# greenhousectrl-latest-expanded.net
KiCad netlist of a schematic drawn in EAGLE
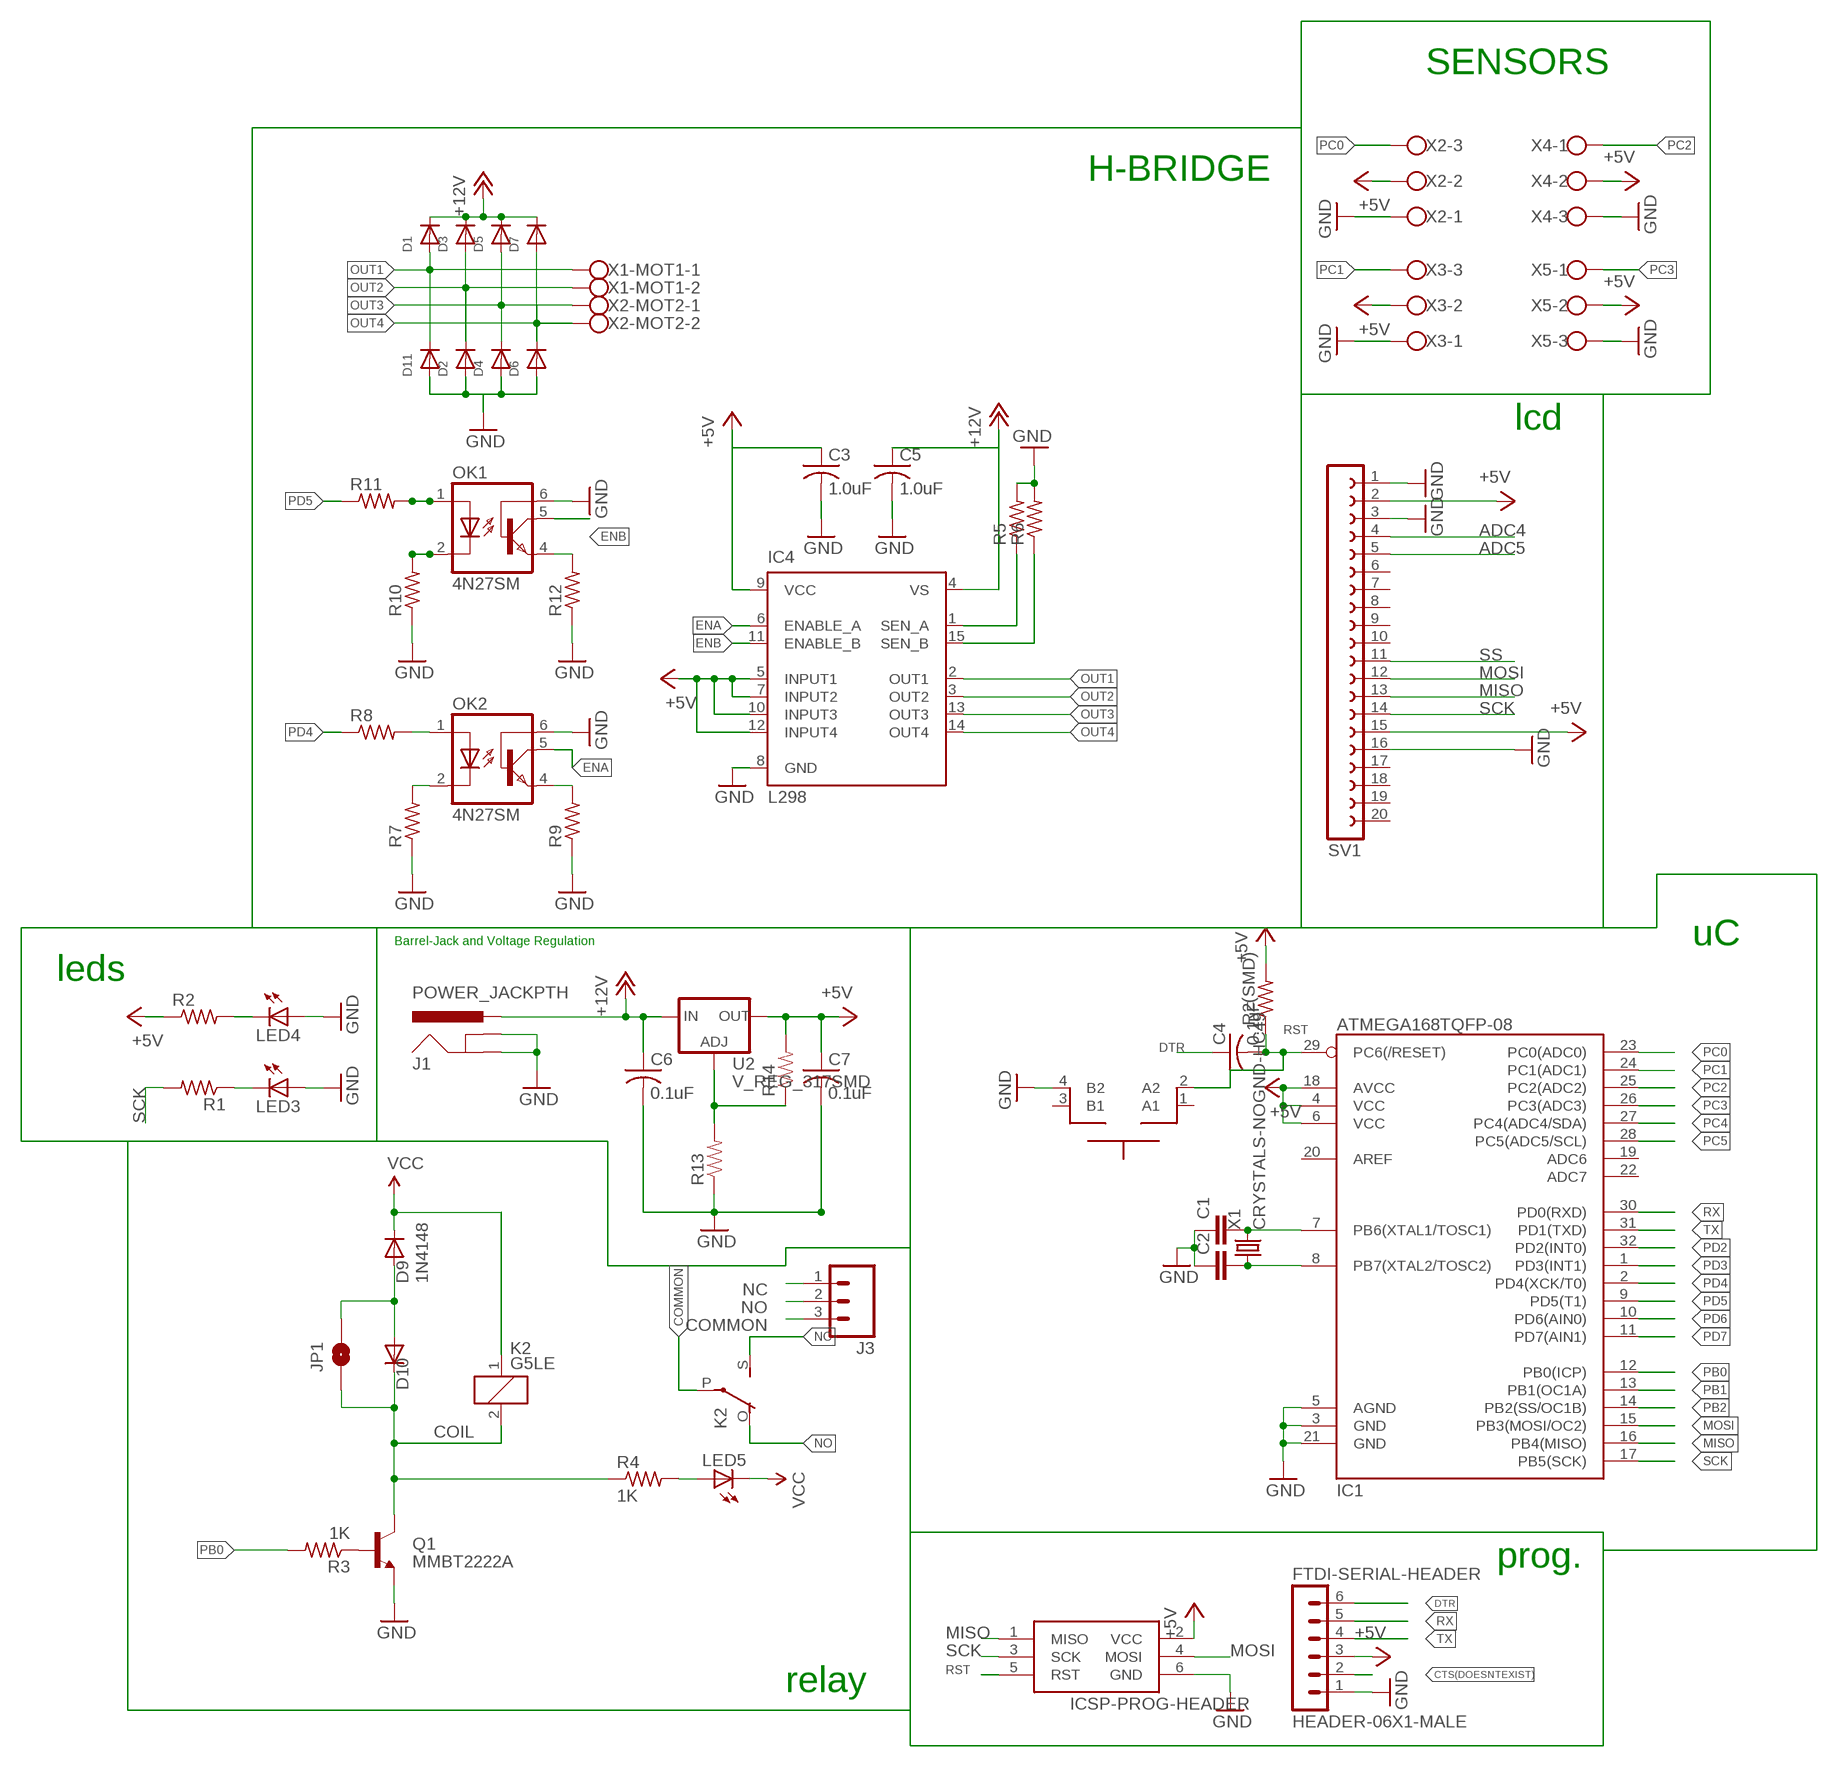
[diagram p0: schematic, sheet 1]

(export (version "E")
  (design (tool "Eeschema 10.0.6"))
  (components
    (comp (ref "C1")
      (value "C-EUC0805")
      (footprint "eagle-import:C0805")
      (libsource (lib "eagle-import") (part "C-EUC0805"))
    )
    (comp (ref "C2")
      (value "C-EUC0805")
      (footprint "eagle-import:C0805")
      (libsource (lib "eagle-import") (part "C-EUC0805"))
    )
    (comp (ref "C3")
      (value "1.0uF")
      (footprint "eagle-import:C0805")
      (libsource (lib "eagle-import") (part "C-USC0805"))
    )
    (comp (ref "C4")
      (value "0.1uF")
      (footprint "eagle-import:C0805")
      (libsource (lib "eagle-import") (part "C-USC0805"))
    )
    (comp (ref "C5")
      (value "1.0uF")
      (footprint "eagle-import:C0805")
      (libsource (lib "eagle-import") (part "C-USC0805"))
    )
    (comp (ref "C6")
      (value "0.1uF")
      (footprint "eagle-import:C0805")
      (libsource (lib "eagle-import") (part "C-USC0805"))
    )
    (comp (ref "C7")
      (value "0.1uF")
      (footprint "eagle-import:C0805")
      (libsource (lib "eagle-import") (part "C-USC0805"))
    )
    (comp (ref "D1")
      (value "DIODESOD-523")
      (footprint "eagle-import:SOD-523")
      (libsource (lib "eagle-import") (part "DIODESOD-523"))
    )
    (comp (ref "D2")
      (value "DIODESOD-523")
      (footprint "eagle-import:SOD-523")
      (libsource (lib "eagle-import") (part "DIODESOD-523"))
    )
    (comp (ref "D3")
      (value "DIODESOD-523")
      (footprint "eagle-import:SOD-523")
      (libsource (lib "eagle-import") (part "DIODESOD-523"))
    )
    (comp (ref "D4")
      (value "DIODESOD-523")
      (footprint "eagle-import:SOD-523")
      (libsource (lib "eagle-import") (part "DIODESOD-523"))
    )
    (comp (ref "D5")
      (value "DIODESOD-523")
      (footprint "eagle-import:SOD-523")
      (libsource (lib "eagle-import") (part "DIODESOD-523"))
    )
    (comp (ref "D6")
      (value "DIODESOD-523")
      (footprint "eagle-import:SOD-523")
      (libsource (lib "eagle-import") (part "DIODESOD-523"))
    )
    (comp (ref "D7")
      (value "DIODESOD-523")
      (footprint "eagle-import:SOD-523")
      (libsource (lib "eagle-import") (part "DIODESOD-523"))
    )
    (comp (ref "D9")
      (value "1N4148")
      (footprint "eagle-import:SOD-323F")
      (libsource (lib "eagle-import") (part "DIODESOD-323F"))
    )
    (comp (ref "D10")
      (value "Zener")
      (footprint "eagle-import:SOD-323F")
      (libsource (lib "eagle-import") (part "DIODESOD-323F"))
    )
    (comp (ref "D11")
      (value "DIODESOD-523")
      (footprint "eagle-import:SOD-523")
      (libsource (lib "eagle-import") (part "DIODESOD-523"))
    )
    (comp (ref "FTDI-SERIAL-HEADER")
      (value "HEADER-06X1-MALE")
      (footprint "eagle-import:06X1-PTH")
      (libsource (lib "eagle-import") (part "HEADER-06X1?-MALE"))
    )
    (comp (ref "IC1")
      (value "ATMEGA168TQFP-08")
      (footprint "eagle-import:TQFP32-08")
      (libsource (lib "eagle-import") (part "ATMEGA168TQFP-08"))
    )
    (comp (ref "IC4")
      (value "L298")
      (footprint "eagle-import:MULTIWATT-15")
      (fields (field (name "MPN") "L298N"))
      (libsource (lib "eagle-import") (part "L298"))
    )
    (comp (ref "ICSP-PROG-HEADER")
      (value "AVRISP-6")
      (footprint "eagle-import:AVRISP")
      (libsource (lib "eagle-import") (part "AVRISP-6"))
    )
    (comp (ref "J1")
      (value "POWER_JACKPTH")
      (footprint "eagle-import:POWER_JACK_PTH")
      (libsource (lib "eagle-import") (part "POWER_JACKPTH"))
    )
    (comp (ref "J3")
      (value "M03-SCREW-5MM")
      (footprint "eagle-import:SCREWTERMINAL-5MM-3")
      (libsource (lib "eagle-import") (part "M03-SCREW-5MM"))
    )
    (comp (ref "JP1")
      (value "JUMPER-PAD-2-NOYES_SILK")
      (footprint "eagle-import:PAD-JUMPER-2-NO_YES_SILK")
      (libsource (lib "eagle-import") (part "JUMPER-PAD-2-NOYES_SILK"))
    )
    (comp (ref "K2")
      (value "G5LE")
      (footprint "eagle-import:G5LE")
      (libsource (lib "eagle-import") (part "G5LE"))
    )
    (comp (ref "LED3")
      (value "LEDCHIP-LED0805")
      (footprint "eagle-import:CHIP-LED0805")
      (libsource (lib "eagle-import") (part "LEDCHIP-LED0805"))
    )
    (comp (ref "LED4")
      (value "LEDCHIP-LED0805")
      (footprint "eagle-import:CHIP-LED0805")
      (libsource (lib "eagle-import") (part "LEDCHIP-LED0805"))
    )
    (comp (ref "LED5")
      (value "LEDCHIP-LED0805")
      (footprint "eagle-import:CHIP-LED0805")
      (libsource (lib "eagle-import") (part "LEDCHIP-LED0805"))
    )
    (comp (ref "OK1")
      (value "4N27SM")
      (footprint "eagle-import:DIL6-SMD")
      (fields (field (name "MF") "FAIRCHILD SEMICONDUCTOR") (field (name "MPN") "4N27S-M"))
      (libsource (lib "eagle-import") (part "4N?MS27"))
    )
    (comp (ref "OK2")
      (value "4N27SM")
      (footprint "eagle-import:DIL6-SMD")
      (fields (field (name "MF") "FAIRCHILD SEMICONDUCTOR") (field (name "MPN") "4N27S-M"))
      (libsource (lib "eagle-import") (part "4N?MS27"))
    )
    (comp (ref "Q1")
      (value "MMBT2222A")
      (footprint "eagle-import:SOT23-3")
      (libsource (lib "eagle-import") (part "TRANSISTOR_NPNMMBT2222A"))
    )
    (comp (ref "R1")
      (value "R-US_M0805")
      (footprint "eagle-import:M0805")
      (libsource (lib "eagle-import") (part "R-US_M0805"))
    )
    (comp (ref "R2")
      (value "R-US_M0805")
      (footprint "eagle-import:M0805")
      (libsource (lib "eagle-import") (part "R-US_M0805"))
    )
    (comp (ref "R2(SMD)")
      (value "R-US_M0805")
      (footprint "eagle-import:M0805")
      (libsource (lib "eagle-import") (part "R-US_M0805"))
    )
    (comp (ref "R3")
      (value "1K")
      (footprint "eagle-import:M0805")
      (libsource (lib "eagle-import") (part "R-US_M0805"))
    )
    (comp (ref "R4")
      (value "1K")
      (footprint "eagle-import:M0805")
      (libsource (lib "eagle-import") (part "R-US_M0805"))
    )
    (comp (ref "R5")
      (value "R-US_M0805")
      (footprint "eagle-import:M0805")
      (libsource (lib "eagle-import") (part "R-US_M0805"))
    )
    (comp (ref "R6")
      (value "R-US_M0805")
      (footprint "eagle-import:M0805")
      (libsource (lib "eagle-import") (part "R-US_M0805"))
    )
    (comp (ref "R7")
      (value "R-US_M0805")
      (footprint "eagle-import:M0805")
      (libsource (lib "eagle-import") (part "R-US_M0805"))
    )
    (comp (ref "R8")
      (value "R-US_M0805")
      (footprint "eagle-import:M0805")
      (libsource (lib "eagle-import") (part "R-US_M0805"))
    )
    (comp (ref "R9")
      (value "R-US_M0805")
      (footprint "eagle-import:M0805")
      (libsource (lib "eagle-import") (part "R-US_M0805"))
    )
    (comp (ref "R10")
      (value "R-US_M0805")
      (footprint "eagle-import:M0805")
      (libsource (lib "eagle-import") (part "R-US_M0805"))
    )
    (comp (ref "R11")
      (value "R-US_M0805")
      (footprint "eagle-import:M0805")
      (libsource (lib "eagle-import") (part "R-US_M0805"))
    )
    (comp (ref "R12")
      (value "R-US_M0805")
      (footprint "eagle-import:M0805")
      (libsource (lib "eagle-import") (part "R-US_M0805"))
    )
    (comp (ref "R13")
      (value "RESISTOR0402")
      (footprint "eagle-import:0402-RES")
      (libsource (lib "eagle-import") (part "RESISTOR0402"))
    )
    (comp (ref "R14")
      (value "RESISTOR0402")
      (footprint "eagle-import:0402-RES")
      (libsource (lib "eagle-import") (part "RESISTOR0402"))
    )
    (comp (ref "SV1")
      (value "FE20-1")
      (footprint "eagle-import:FE20")
      (libsource (lib "eagle-import") (part "FE20-1"))
    )
    (comp (ref "SW2")
      (value "MOMENTARYBUTTON")
      (footprint "eagle-import:SPST_NO_SMD")
      (libsource (lib "eagle-import") (part "MOMENTARYBUTTON"))
    )
    (comp (ref "U2")
      (value "V_REG_317SMD")
      (footprint "eagle-import:SOT223")
      (libsource (lib "eagle-import") (part "V_REG_317SMD"))
    )
    (comp (ref "X1")
      (value "CRYSTALS-NOGND-HC49")
      (footprint "eagle-import:HC49")
      (libsource (lib "eagle-import") (part "CRYSTALS-NOGND-HC49"))
    )
    (comp (ref "X1-MOT1")
      (value "W237-102")
      (footprint "eagle-import:W237-102")
      (fields (field (name "MPN") "237-102"))
      (libsource (lib "eagle-import") (part "W237-102"))
    )
    (comp (ref "X2")
      (value "1X03_5MM_SCREW")
      (footprint "eagle-import:W237-103")
      (fields (field (name "MPN") "237-103"))
      (libsource (lib "eagle-import") (part "1X03_5MM_SCREW"))
    )
    (comp (ref "X2-MOT2")
      (value "W237-102")
      (footprint "eagle-import:W237-102")
      (fields (field (name "MPN") "237-102"))
      (libsource (lib "eagle-import") (part "W237-102"))
    )
    (comp (ref "X3")
      (value "1X03_5MM_SCREW")
      (footprint "eagle-import:W237-103")
      (fields (field (name "MPN") "237-103"))
      (libsource (lib "eagle-import") (part "1X03_5MM_SCREW"))
    )
    (comp (ref "X4")
      (value "1X03_5MM_SCREW")
      (footprint "eagle-import:W237-103")
      (fields (field (name "MPN") "237-103"))
      (libsource (lib "eagle-import") (part "1X03_5MM_SCREW"))
    )
    (comp (ref "X5")
      (value "1X03_5MM_SCREW")
      (footprint "eagle-import:W237-103")
      (fields (field (name "MPN") "237-103"))
      (libsource (lib "eagle-import") (part "1X03_5MM_SCREW"))
    )
  )
  (nets
    (net (code "1") (name "+5V") (class "Default")
      (node (ref "C3") (pin "1") (pinfunction "1_1") (pintype "passive"))
      (node (ref "C7") (pin "1") (pinfunction "1_1") (pintype "passive"))
      (node (ref "FTDI-SERIAL-HEADER") (pin "3") (pinfunction "3_3") (pintype "passive"))
      (node (ref "IC1") (pin "18") (pinfunction "AVCC_18") (pintype "bidirectional"))
      (node (ref "IC1") (pin "4") (pinfunction "VCC_4") (pintype "bidirectional"))
      (node (ref "IC1") (pin "6") (pinfunction "VCC_6") (pintype "bidirectional"))
      (node (ref "IC4") (pin "10") (pinfunction "INPUT3_10") (pintype "input"))
      (node (ref "IC4") (pin "12") (pinfunction "INPUT4_12") (pintype "input"))
      (node (ref "IC4") (pin "5") (pinfunction "INPUT1_5") (pintype "input"))
      (node (ref "IC4") (pin "7") (pinfunction "INPUT2_7") (pintype "input"))
      (node (ref "IC4") (pin "9") (pinfunction "VCC_9") (pintype "power_in"))
      (node (ref "ICSP-PROG-HEADER") (pin "2") (pinfunction "VCC_2") (pintype "power_in"))
      (node (ref "R14") (pin "2") (pinfunction "2_2") (pintype "passive"))
      (node (ref "R2") (pin "1") (pinfunction "1_1") (pintype "passive"))
      (node (ref "R2(SMD)") (pin "2") (pinfunction "2_2") (pintype "passive"))
      (node (ref "SV1") (pin "15") (pinfunction "15_15") (pintype "passive"))
      (node (ref "SV1") (pin "2") (pinfunction "2_2") (pintype "passive"))
      (node (ref "U2") (pin "2") (pinfunction "OUT_2") (pintype "output"))
      (node (ref "X2") (pin "2") (pinfunction "KL_2") (pintype "passive"))
      (node (ref "X3") (pin "2") (pinfunction "KL_2") (pintype "passive"))
      (node (ref "X4") (pin "2") (pinfunction "KL_2") (pintype "passive"))
      (node (ref "X5") (pin "2") (pinfunction "KL_2") (pintype "passive"))
    )
    (net (code "2") (name "+12V") (class "Default")
      (node (ref "C5") (pin "1") (pinfunction "1_1") (pintype "passive"))
      (node (ref "C6") (pin "1") (pinfunction "1_1") (pintype "passive"))
      (node (ref "D1") (pin "K") (pinfunction "C_K") (pintype "passive"))
      (node (ref "D3") (pin "K") (pinfunction "C_K") (pintype "passive"))
      (node (ref "D5") (pin "K") (pinfunction "C_K") (pintype "passive"))
      (node (ref "D7") (pin "K") (pinfunction "C_K") (pintype "passive"))
      (node (ref "IC4") (pin "4") (pinfunction "VS_4") (pintype "power_in"))
      (node (ref "J1") (pin "PWR") (pinfunction "PWR_PWR") (pintype "bidirectional"))
      (node (ref "U2") (pin "3") (pinfunction "IN_3") (pintype "input"))
    )
    (net (code "3") (name "/ADC4") (class "Default")
      (node (ref "SV1") (pin "4") (pinfunction "4_4") (pintype "passive"))
    )
    (net (code "4") (name "/ADC5") (class "Default")
      (node (ref "SV1") (pin "5") (pinfunction "5_5") (pintype "passive"))
    )
    (net (code "5") (name "/COIL") (class "Default")
      (node (ref "D10") (pin "C") (pinfunction "C_C") (pintype "passive"))
      (node (ref "JP1") (pin "1") (pinfunction "1_1") (pintype "passive"))
      (node (ref "K2") (pin "2") (pinfunction "2_2") (pintype "passive"))
      (node (ref "Q1") (pin "3") (pinfunction "C_3") (pintype "passive"))
      (node (ref "R4") (pin "1") (pinfunction "1_1") (pintype "passive"))
    )
    (net (code "6") (name "/RST") (class "Default")
      (node (ref "C4") (pin "2") (pinfunction "2_2") (pintype "passive"))
      (node (ref "IC1") (pin "29") (pinfunction "PC6(/RESET)_29") (pintype "bidirectional"))
      (node (ref "ICSP-PROG-HEADER") (pin "5") (pinfunction "RST_5") (pintype "output"))
      (node (ref "R2(SMD)") (pin "1") (pinfunction "1_1") (pintype "passive"))
      (node (ref "SW2") (pin "2") (pinfunction "A2_2") (pintype "bidirectional"))
    )
    (net (code "7") (name "/SS") (class "Default")
      (node (ref "SV1") (pin "11") (pinfunction "11_11") (pintype "passive"))
    )
    (net (code "8") (name "COMMON") (class "Default")
      (node (ref "J3") (pin "3") (pinfunction "3_3") (pintype "passive"))
      (node (ref "K2") (pin "P") (pinfunction "P_P") (pintype "passive"))
    )
    (net (code "9") (name "CTS(DOESNTEXIST)") (class "Default")
      (node (ref "FTDI-SERIAL-HEADER") (pin "2") (pinfunction "2_2") (pintype "passive"))
    )
    (net (code "10") (name "DTR") (class "Default")
      (node (ref "C4") (pin "1") (pinfunction "1_1") (pintype "passive"))
      (node (ref "FTDI-SERIAL-HEADER") (pin "6") (pinfunction "6_6") (pintype "passive"))
    )
    (net (code "11") (name "ENA") (class "Default")
      (node (ref "IC4") (pin "6") (pinfunction "ENABLE_A_6") (pintype "input"))
      (node (ref "OK2") (pin "5") (pinfunction "COL_5") (pintype "passive"))
    )
    (net (code "12") (name "ENB") (class "Default")
      (node (ref "IC4") (pin "11") (pinfunction "ENABLE_B_11") (pintype "input"))
      (node (ref "OK1") (pin "5") (pinfunction "COL_5") (pintype "passive"))
    )
    (net (code "13") (name "GND") (class "Default")
      (node (ref "C1") (pin "1") (pinfunction "1_1") (pintype "passive"))
      (node (ref "C2") (pin "1") (pinfunction "1_1") (pintype "passive"))
      (node (ref "C3") (pin "2") (pinfunction "2_2") (pintype "passive"))
      (node (ref "C5") (pin "2") (pinfunction "2_2") (pintype "passive"))
      (node (ref "C6") (pin "2") (pinfunction "2_2") (pintype "passive"))
      (node (ref "C7") (pin "2") (pinfunction "2_2") (pintype "passive"))
      (node (ref "D11") (pin "A") (pinfunction "A_A") (pintype "passive"))
      (node (ref "D2") (pin "A") (pinfunction "A_A") (pintype "passive"))
      (node (ref "D4") (pin "A") (pinfunction "A_A") (pintype "passive"))
      (node (ref "D6") (pin "A") (pinfunction "A_A") (pintype "passive"))
      (node (ref "FTDI-SERIAL-HEADER") (pin "1") (pinfunction "1_1") (pintype "passive"))
      (node (ref "IC1") (pin "21") (pinfunction "GND_21") (pintype "bidirectional"))
      (node (ref "IC1") (pin "3") (pinfunction "GND_3") (pintype "bidirectional"))
      (node (ref "IC1") (pin "5") (pinfunction "AGND_5") (pintype "bidirectional"))
      (node (ref "IC4") (pin "8") (pinfunction "GND_8") (pintype "power_in"))
      (node (ref "ICSP-PROG-HEADER") (pin "6") (pinfunction "GND_6") (pintype "power_in"))
      (node (ref "J1") (pin "GND") (pinfunction "GND_GND") (pintype "bidirectional"))
      (node (ref "J1") (pin "GNDBREAK") (pinfunction "GNDBREAK_GNDBREAK") (pintype "bidirectional"))
      (node (ref "LED3") (pin "A") (pinfunction "A_A") (pintype "passive"))
      (node (ref "LED4") (pin "A") (pinfunction "A_A") (pintype "passive"))
      (node (ref "OK1") (pin "6") (pinfunction "BAS_6") (pintype "passive"))
      (node (ref "OK2") (pin "6") (pinfunction "BAS_6") (pintype "passive"))
      (node (ref "Q1") (pin "2") (pinfunction "E_2") (pintype "passive"))
      (node (ref "R10") (pin "1") (pinfunction "1_1") (pintype "passive"))
      (node (ref "R12") (pin "1") (pinfunction "1_1") (pintype "passive"))
      (node (ref "R13") (pin "1") (pinfunction "1_1") (pintype "passive"))
      (node (ref "R5") (pin "2") (pinfunction "2_2") (pintype "passive"))
      (node (ref "R6") (pin "2") (pinfunction "2_2") (pintype "passive"))
      (node (ref "R7") (pin "1") (pinfunction "1_1") (pintype "passive"))
      (node (ref "R9") (pin "1") (pinfunction "1_1") (pintype "passive"))
      (node (ref "SV1") (pin "1") (pinfunction "1_1") (pintype "passive"))
      (node (ref "SV1") (pin "16") (pinfunction "16_16") (pintype "passive"))
      (node (ref "SV1") (pin "3") (pinfunction "3_3") (pintype "passive"))
      (node (ref "SW2") (pin "4") (pinfunction "B2_4") (pintype "bidirectional"))
      (node (ref "X2") (pin "1") (pinfunction "KL_1") (pintype "passive"))
      (node (ref "X3") (pin "1") (pinfunction "KL_1") (pintype "passive"))
      (node (ref "X4") (pin "3") (pinfunction "KL_3") (pintype "passive"))
      (node (ref "X5") (pin "3") (pinfunction "KL_3") (pintype "passive"))
    )
    (net (code "14") (name "MISO") (class "Default")
      (node (ref "IC1") (pin "16") (pinfunction "PB4(MISO)_16") (pintype "bidirectional"))
      (node (ref "ICSP-PROG-HEADER") (pin "1") (pinfunction "MISO_1") (pintype "input"))
      (node (ref "SV1") (pin "13") (pinfunction "13_13") (pintype "passive"))
    )
    (net (code "15") (name "MOSI") (class "Default")
      (node (ref "IC1") (pin "15") (pinfunction "PB3(MOSI/OC2)_15") (pintype "bidirectional"))
      (node (ref "ICSP-PROG-HEADER") (pin "4") (pinfunction "MOSI_4") (pintype "output"))
      (node (ref "SV1") (pin "12") (pinfunction "12_12") (pintype "passive"))
    )
    (net (code "16") (name "NC") (class "Default")
      (node (ref "J3") (pin "1") (pinfunction "1_1") (pintype "passive"))
      (node (ref "K2") (pin "S") (pinfunction "S_S") (pintype "passive"))
    )
    (net (code "17") (name "NO") (class "Default")
      (node (ref "J3") (pin "2") (pinfunction "2_2") (pintype "passive"))
      (node (ref "K2") (pin "O") (pinfunction "O_O") (pintype "passive"))
    )
    (net (code "18") (name "Net-(D10-PadA)") (class "Default")
      (node (ref "D10") (pin "A") (pinfunction "A_A") (pintype "passive"))
      (node (ref "D9") (pin "A") (pinfunction "A_A") (pintype "passive"))
      (node (ref "JP1") (pin "2") (pinfunction "2_2") (pintype "passive"))
    )
    (net (code "19") (name "Net-(IC1-PB6(XTAL1{slash}TOSC1))") (class "Default")
      (node (ref "C1") (pin "2") (pinfunction "2_2") (pintype "passive"))
      (node (ref "IC1") (pin "7") (pinfunction "PB6(XTAL1/TOSC1)_7") (pintype "bidirectional"))
      (node (ref "X1") (pin "2") (pinfunction "2_2") (pintype "passive"))
    )
    (net (code "20") (name "Net-(IC1-PB7(XTAL2{slash}TOSC2))") (class "Default")
      (node (ref "C2") (pin "2") (pinfunction "2_2") (pintype "passive"))
      (node (ref "IC1") (pin "8") (pinfunction "PB7(XTAL2/TOSC2)_8") (pintype "bidirectional"))
      (node (ref "X1") (pin "1") (pinfunction "1_1") (pintype "passive"))
    )
    (net (code "21") (name "Net-(IC4-SEN_A)") (class "Default")
      (node (ref "IC4") (pin "1") (pinfunction "SEN_A_1") (pintype "input"))
      (node (ref "R5") (pin "1") (pinfunction "1_1") (pintype "passive"))
    )
    (net (code "22") (name "Net-(IC4-SEN_B)") (class "Default")
      (node (ref "IC4") (pin "15") (pinfunction "SEN_B_15") (pintype "input"))
      (node (ref "R6") (pin "1") (pinfunction "1_1") (pintype "passive"))
    )
    (net (code "23") (name "Net-(LED3-PadC)") (class "Default")
      (node (ref "LED3") (pin "C") (pinfunction "C_C") (pintype "passive"))
      (node (ref "R1") (pin "1") (pinfunction "1_1") (pintype "passive"))
    )
    (net (code "24") (name "Net-(LED4-PadC)") (class "Default")
      (node (ref "LED4") (pin "C") (pinfunction "C_C") (pintype "passive"))
      (node (ref "R2") (pin "2") (pinfunction "2_2") (pintype "passive"))
    )
    (net (code "25") (name "Net-(LED5-PadA)") (class "Default")
      (node (ref "LED5") (pin "A") (pinfunction "A_A") (pintype "passive"))
      (node (ref "R4") (pin "2") (pinfunction "2_2") (pintype "passive"))
    )
    (net (code "26") (name "Net-(OK1-A)") (class "Default")
      (node (ref "OK1") (pin "1") (pinfunction "A_1") (pintype "passive"))
      (node (ref "R11") (pin "2") (pinfunction "2_2") (pintype "passive"))
    )
    (net (code "27") (name "Net-(OK1-C)") (class "Default")
      (node (ref "OK1") (pin "2") (pinfunction "C_2") (pintype "passive"))
      (node (ref "R10") (pin "2") (pinfunction "2_2") (pintype "passive"))
    )
    (net (code "28") (name "Net-(OK1-EMI)") (class "Default")
      (node (ref "OK1") (pin "4") (pinfunction "EMI_4") (pintype "passive"))
      (node (ref "R12") (pin "2") (pinfunction "2_2") (pintype "passive"))
    )
    (net (code "29") (name "Net-(OK2-A)") (class "Default")
      (node (ref "OK2") (pin "1") (pinfunction "A_1") (pintype "passive"))
      (node (ref "R8") (pin "2") (pinfunction "2_2") (pintype "passive"))
    )
    (net (code "30") (name "Net-(OK2-C)") (class "Default")
      (node (ref "OK2") (pin "2") (pinfunction "C_2") (pintype "passive"))
      (node (ref "R7") (pin "2") (pinfunction "2_2") (pintype "passive"))
    )
    (net (code "31") (name "Net-(OK2-EMI)") (class "Default")
      (node (ref "OK2") (pin "4") (pinfunction "EMI_4") (pintype "passive"))
      (node (ref "R9") (pin "2") (pinfunction "2_2") (pintype "passive"))
    )
    (net (code "32") (name "Net-(Q1-B)") (class "Default")
      (node (ref "Q1") (pin "1") (pinfunction "B_1") (pintype "passive"))
      (node (ref "R3") (pin "1") (pinfunction "1_1") (pintype "passive"))
    )
    (net (code "33") (name "Net-(U2-ADJ)") (class "Default")
      (node (ref "R13") (pin "2") (pinfunction "2_2") (pintype "passive"))
      (node (ref "R14") (pin "1") (pinfunction "1_1") (pintype "passive"))
      (node (ref "U2") (pin "1") (pinfunction "ADJ_1") (pintype "input"))
    )
    (net (code "34") (name "OUT1") (class "Default")
      (node (ref "D1") (pin "A") (pinfunction "A_A") (pintype "passive"))
      (node (ref "D11") (pin "K") (pinfunction "C_K") (pintype "passive"))
      (node (ref "IC4") (pin "2") (pinfunction "OUT1_2") (pintype "output"))
      (node (ref "X1-MOT1") (pin "1") (pinfunction "KL_1") (pintype "passive"))
    )
    (net (code "35") (name "OUT2") (class "Default")
      (node (ref "D2") (pin "K") (pinfunction "C_K") (pintype "passive"))
      (node (ref "D3") (pin "A") (pinfunction "A_A") (pintype "passive"))
      (node (ref "IC4") (pin "3") (pinfunction "OUT2_3") (pintype "output"))
      (node (ref "X1-MOT1") (pin "2") (pinfunction "KL_2") (pintype "passive"))
    )
    (net (code "36") (name "OUT3") (class "Default")
      (node (ref "D4") (pin "K") (pinfunction "C_K") (pintype "passive"))
      (node (ref "D5") (pin "A") (pinfunction "A_A") (pintype "passive"))
      (node (ref "IC4") (pin "13") (pinfunction "OUT3_13") (pintype "output"))
      (node (ref "X2-MOT2") (pin "1") (pinfunction "KL_1") (pintype "passive"))
    )
    (net (code "37") (name "OUT4") (class "Default")
      (node (ref "D6") (pin "K") (pinfunction "C_K") (pintype "passive"))
      (node (ref "D7") (pin "A") (pinfunction "A_A") (pintype "passive"))
      (node (ref "IC4") (pin "14") (pinfunction "OUT4_14") (pintype "output"))
      (node (ref "X2-MOT2") (pin "2") (pinfunction "KL_2") (pintype "passive"))
    )
    (net (code "38") (name "PB0") (class "Default")
      (node (ref "IC1") (pin "12") (pinfunction "PB0(ICP)_12") (pintype "bidirectional"))
      (node (ref "R3") (pin "2") (pinfunction "2_2") (pintype "passive"))
    )
    (net (code "39") (name "PB1") (class "Default")
      (node (ref "IC1") (pin "13") (pinfunction "PB1(OC1A)_13") (pintype "bidirectional"))
    )
    (net (code "40") (name "PB2") (class "Default")
      (node (ref "IC1") (pin "14") (pinfunction "PB2(SS/OC1B)_14") (pintype "bidirectional"))
    )
    (net (code "41") (name "PC0") (class "Default")
      (node (ref "IC1") (pin "23") (pinfunction "PC0(ADC0)_23") (pintype "bidirectional"))
      (node (ref "X2") (pin "3") (pinfunction "KL_3") (pintype "passive"))
    )
    (net (code "42") (name "PC1") (class "Default")
      (node (ref "IC1") (pin "24") (pinfunction "PC1(ADC1)_24") (pintype "bidirectional"))
      (node (ref "X3") (pin "3") (pinfunction "KL_3") (pintype "passive"))
    )
    (net (code "43") (name "PC2") (class "Default")
      (node (ref "IC1") (pin "25") (pinfunction "PC2(ADC2)_25") (pintype "bidirectional"))
      (node (ref "X4") (pin "1") (pinfunction "KL_1") (pintype "passive"))
    )
    (net (code "44") (name "PC3") (class "Default")
      (node (ref "IC1") (pin "26") (pinfunction "PC3(ADC3)_26") (pintype "bidirectional"))
      (node (ref "X5") (pin "1") (pinfunction "KL_1") (pintype "passive"))
    )
    (net (code "45") (name "PC4") (class "Default")
      (node (ref "IC1") (pin "27") (pinfunction "PC4(ADC4/SDA)_27") (pintype "bidirectional"))
    )
    (net (code "46") (name "PC5") (class "Default")
      (node (ref "IC1") (pin "28") (pinfunction "PC5(ADC5/SCL)_28") (pintype "bidirectional"))
    )
    (net (code "47") (name "PD2") (class "Default")
      (node (ref "IC1") (pin "32") (pinfunction "PD2(INT0)_32") (pintype "bidirectional"))
    )
    (net (code "48") (name "PD3") (class "Default")
      (node (ref "IC1") (pin "1") (pinfunction "PD3(INT1)_1") (pintype "bidirectional"))
    )
    (net (code "49") (name "PD4") (class "Default")
      (node (ref "IC1") (pin "2") (pinfunction "PD4(XCK/T0)_2") (pintype "bidirectional"))
      (node (ref "R8") (pin "1") (pinfunction "1_1") (pintype "passive"))
    )
    (net (code "50") (name "PD5") (class "Default")
      (node (ref "IC1") (pin "9") (pinfunction "PD5(T1)_9") (pintype "bidirectional"))
      (node (ref "R11") (pin "1") (pinfunction "1_1") (pintype "passive"))
    )
    (net (code "51") (name "PD6") (class "Default")
      (node (ref "IC1") (pin "10") (pinfunction "PD6(AIN0)_10") (pintype "bidirectional"))
    )
    (net (code "52") (name "PD7") (class "Default")
      (node (ref "IC1") (pin "11") (pinfunction "PD7(AIN1)_11") (pintype "bidirectional"))
    )
    (net (code "53") (name "RX") (class "Default")
      (node (ref "FTDI-SERIAL-HEADER") (pin "5") (pinfunction "5_5") (pintype "passive"))
      (node (ref "IC1") (pin "30") (pinfunction "PD0(RXD)_30") (pintype "bidirectional"))
    )
    (net (code "54") (name "SCK") (class "Default")
      (node (ref "IC1") (pin "17") (pinfunction "PB5(SCK)_17") (pintype "bidirectional"))
      (node (ref "ICSP-PROG-HEADER") (pin "3") (pinfunction "SCK_3") (pintype "output"))
      (node (ref "R1") (pin "2") (pinfunction "2_2") (pintype "passive"))
      (node (ref "SV1") (pin "14") (pinfunction "14_14") (pintype "passive"))
    )
    (net (code "55") (name "TX") (class "Default")
      (node (ref "FTDI-SERIAL-HEADER") (pin "4") (pinfunction "4_4") (pintype "passive"))
      (node (ref "IC1") (pin "31") (pinfunction "PD1(TXD)_31") (pintype "bidirectional"))
    )
    (net (code "56") (name "VCC") (class "Default")
      (node (ref "D9") (pin "C") (pinfunction "C_C") (pintype "passive"))
      (node (ref "K2") (pin "1") (pinfunction "1_1") (pintype "passive"))
      (node (ref "LED5") (pin "C") (pinfunction "C_C") (pintype "passive"))
    )
    (net (code "57") (name "unconnected-(IC1-ADC6-Pad19)") (class "Default")
      (node (ref "IC1") (pin "19") (pinfunction "ADC6_19") (pintype "bidirectional"))
    )
    (net (code "58") (name "unconnected-(IC1-ADC7-Pad22)") (class "Default")
      (node (ref "IC1") (pin "22") (pinfunction "ADC7_22") (pintype "bidirectional"))
    )
    (net (code "59") (name "unconnected-(IC1-AREF-Pad20)") (class "Default")
      (node (ref "IC1") (pin "20") (pinfunction "AREF_20") (pintype "bidirectional"))
    )
    (net (code "60") (name "unconnected-(SV1-Pad6)") (class "Default")
      (node (ref "SV1") (pin "6") (pinfunction "6_6") (pintype "passive"))
    )
    (net (code "61") (name "unconnected-(SV1-Pad7)") (class "Default")
      (node (ref "SV1") (pin "7") (pinfunction "7_7") (pintype "passive"))
    )
    (net (code "62") (name "unconnected-(SV1-Pad8)") (class "Default")
      (node (ref "SV1") (pin "8") (pinfunction "8_8") (pintype "passive"))
    )
    (net (code "63") (name "unconnected-(SV1-Pad9)") (class "Default")
      (node (ref "SV1") (pin "9") (pinfunction "9_9") (pintype "passive"))
    )
    (net (code "64") (name "unconnected-(SV1-Pad10)") (class "Default")
      (node (ref "SV1") (pin "10") (pinfunction "10_10") (pintype "passive"))
    )
    (net (code "65") (name "unconnected-(SV1-Pad17)") (class "Default")
      (node (ref "SV1") (pin "17") (pinfunction "17_17") (pintype "passive"))
    )
    (net (code "66") (name "unconnected-(SV1-Pad18)") (class "Default")
      (node (ref "SV1") (pin "18") (pinfunction "18_18") (pintype "passive"))
    )
    (net (code "67") (name "unconnected-(SV1-Pad19)") (class "Default")
      (node (ref "SV1") (pin "19") (pinfunction "19_19") (pintype "passive"))
    )
    (net (code "68") (name "unconnected-(SV1-Pad20)") (class "Default")
      (node (ref "SV1") (pin "20") (pinfunction "20_20") (pintype "passive"))
    )
    (net (code "69") (name "unconnected-(SW2-A1-Pad1)") (class "Default")
      (node (ref "SW2") (pin "1") (pinfunction "A1_1") (pintype "bidirectional"))
    )
    (net (code "70") (name "unconnected-(SW2-B1-Pad3)") (class "Default")
      (node (ref "SW2") (pin "3") (pinfunction "B1_3") (pintype "bidirectional"))
    )
  )
)
